# kicker_controller.net
KiCad netlist of a schematic drawn in EAGLE
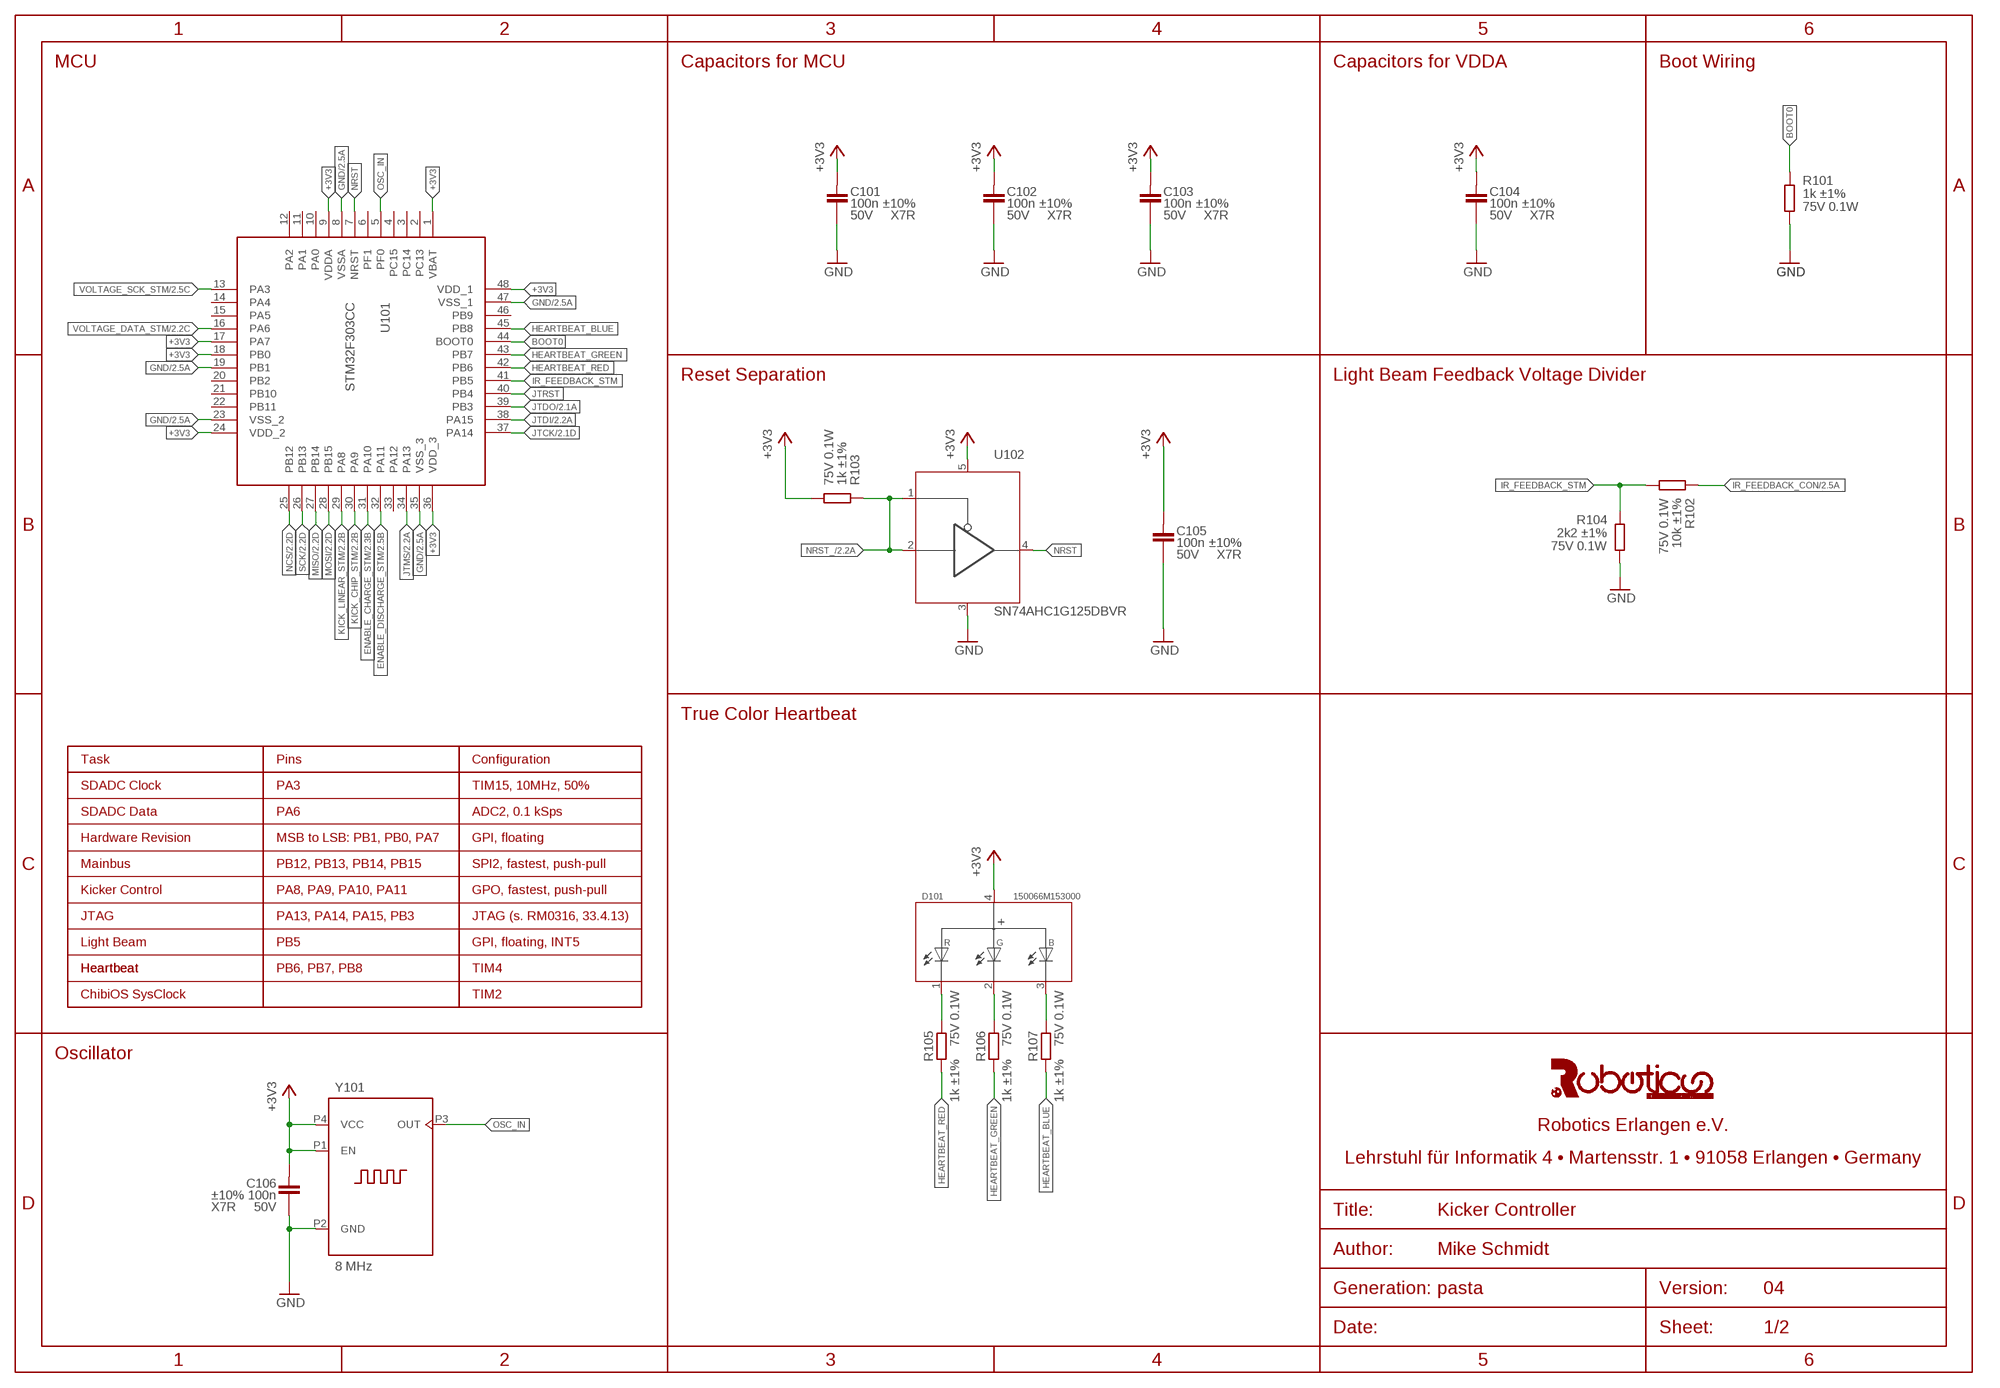
[diagram p0: schematic, sheet 1]
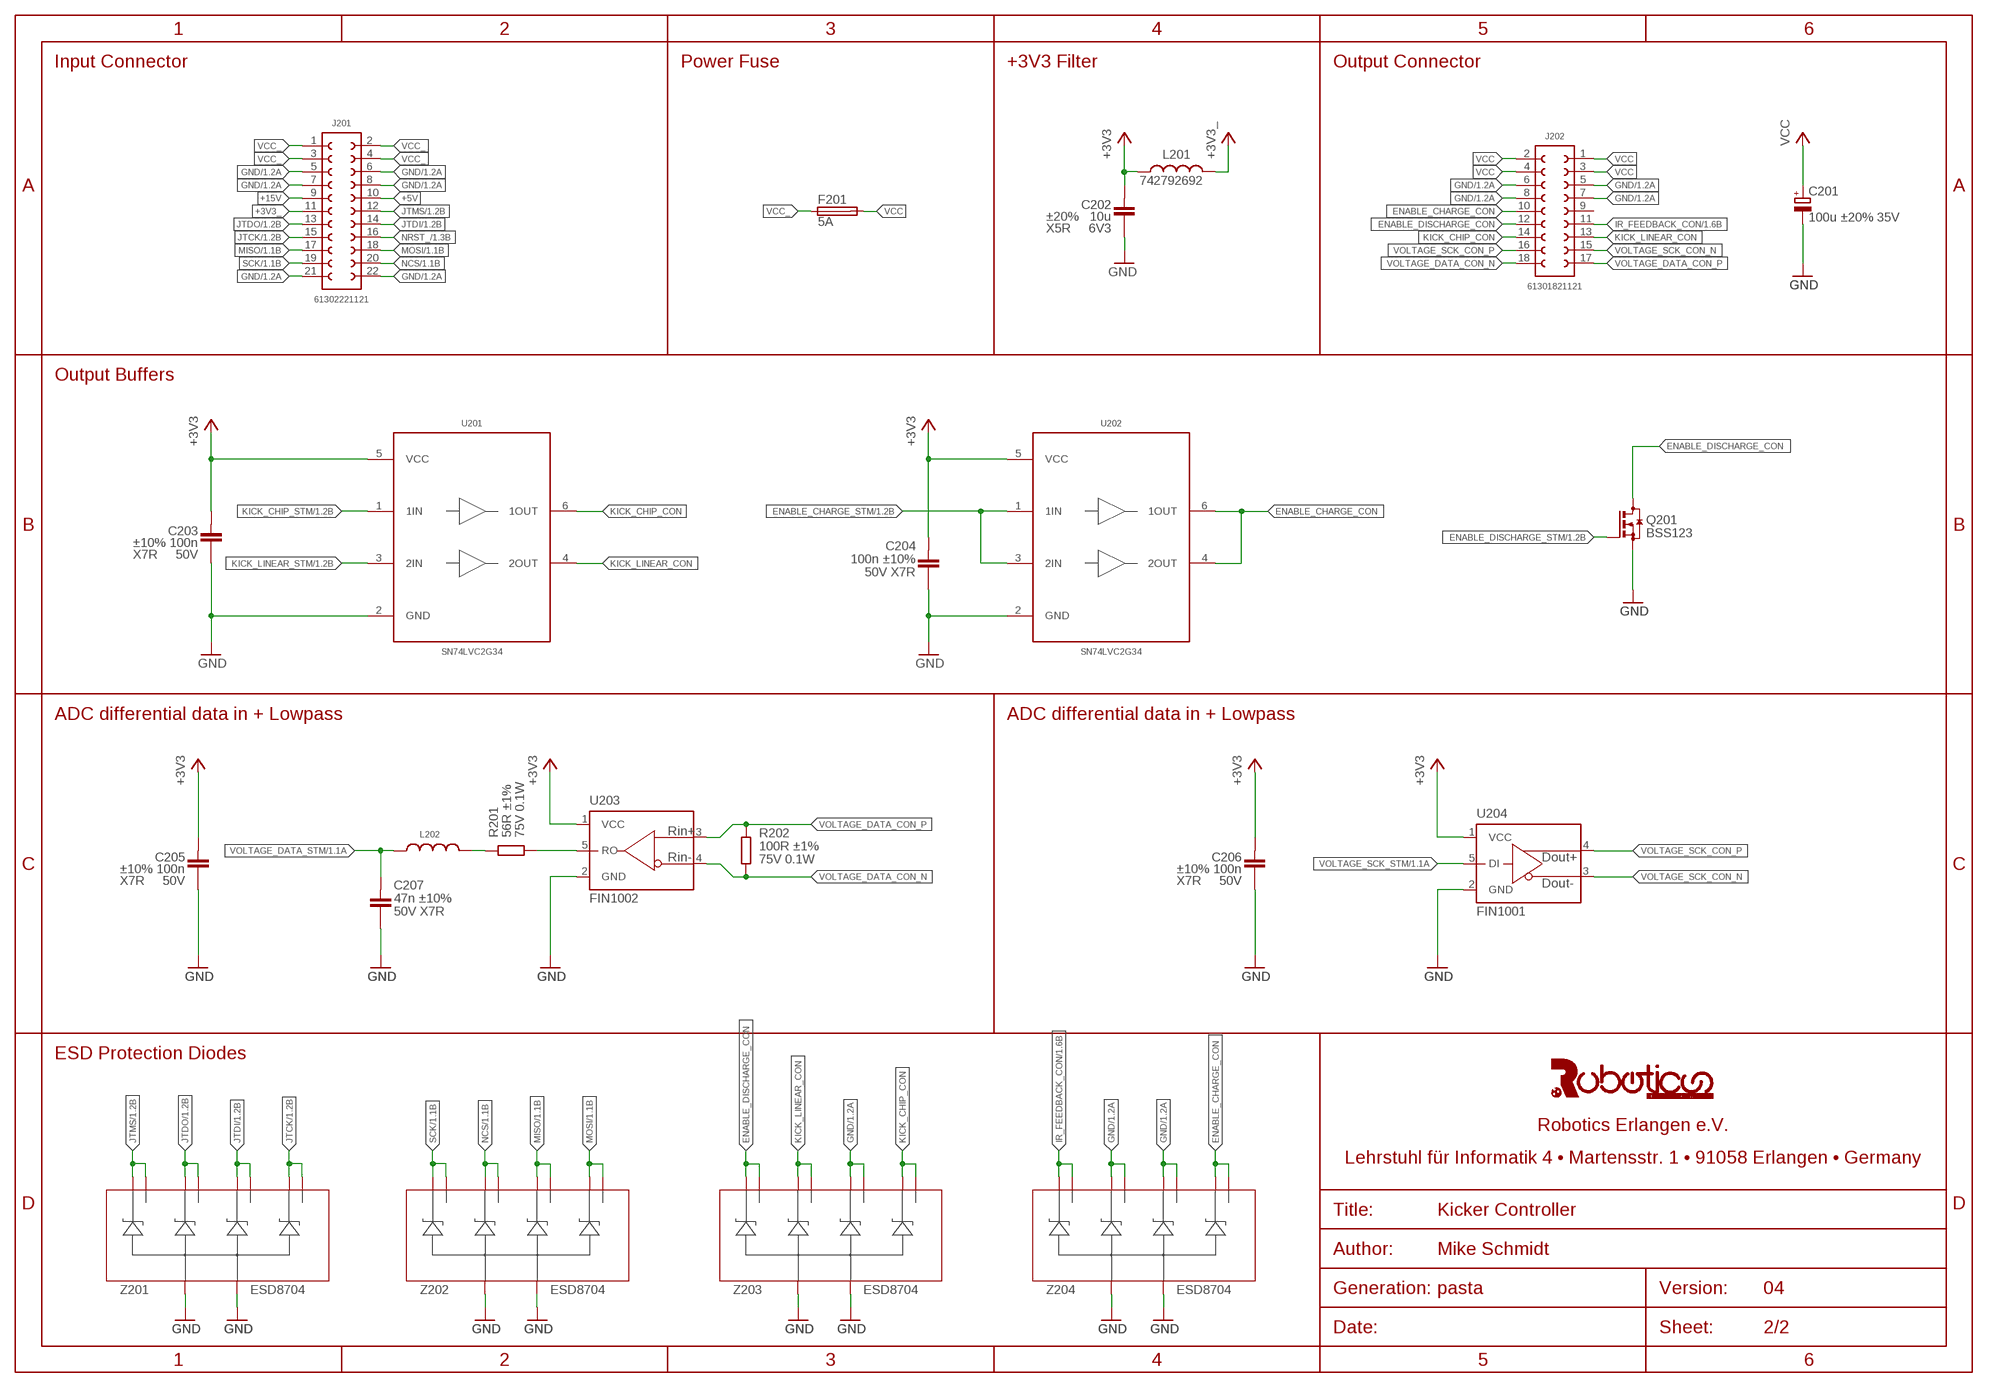
[diagram p1: schematic, sheet 2]

(export (version "E")
  (design (tool "Eeschema 10.0.6"))
  (components
    (comp (ref "C201")
      (value "100u ±20% 35V")
      (footprint "eagle-import:865080545012")
      (fields (field (name "MF") "Würth Elektronik") (field (name "MPN") "865080545012"))
      (libsource (lib "eagle-import") (part "865080545012"))
    )
    (comp (ref "C202")
      (value "10u ±20% 6V3 X5R")
      (footprint "eagle-import:C0603")
      (fields
        (field (name "CAPACITANCE") "10u")
        (field (name "DIELECTRIC") "X5R")
        (field (name "MF") "Würth Elektronik")
        (field (name "MPN") "885012106006")
        (field (name "TOLERANCE") "±20%")
        (field (name "VOLTAGE") "6V3")
      )
      (libsource (lib "eagle-import") (part "C(?)060310UF,6.3V,"))
    )
    (comp (ref "C203")
      (value "100n ±10% 50V X7R")
      (footprint "eagle-import:C0603")
      (fields
        (field (name "CAPACITANCE") "100n")
        (field (name "DIELECTRIC") "X7R")
        (field (name "MF") "Würth Elektronik")
        (field (name "MPN") "885012206095")
        (field (name "TOLERANCE") "±10%")
        (field (name "VOLTAGE") "50V")
      )
      (libsource (lib "eagle-import") (part "C(?)0603100NF,50V,"))
    )
    (comp (ref "C204")
      (value "100n ±10% 50V X7R")
      (footprint "eagle-import:C0603")
      (fields
        (field (name "LINE1") "100n ±10%")
        (field (name "LINE2") "50V X7R")
        (field (name "MF") "Würth Elektronik")
        (field (name "MPN") "885012206095")
        (field (name "TOLERANCE") "±10%")
      )
      (libsource (lib "eagle-import") (part "C(?)0603100NF,50V,"))
    )
    (comp (ref "C205")
      (value "100n ±10% 50V X7R")
      (footprint "eagle-import:C0603")
      (fields
        (field (name "CAPACITANCE") "100n")
        (field (name "DIELECTRIC") "X7R")
        (field (name "MF") "Würth Elektronik")
        (field (name "MPN") "885012206095")
        (field (name "TOLERANCE") "±10%")
        (field (name "VOLTAGE") "50V")
      )
      (libsource (lib "eagle-import") (part "C(?)0603100NF,50V,"))
    )
    (comp (ref "C206")
      (value "100n ±10% 50V X7R")
      (footprint "eagle-import:C0603")
      (fields
        (field (name "CAPACITANCE") "100n")
        (field (name "DIELECTRIC") "X7R")
        (field (name "MF") "Würth Elektronik")
        (field (name "MPN") "885012206095")
        (field (name "TOLERANCE") "±10%")
        (field (name "VOLTAGE") "50V")
      )
      (libsource (lib "eagle-import") (part "C(?)0603100NF,50V,"))
    )
    (comp (ref "C207")
      (value "47n ±10% 50V X7R")
      (footprint "eagle-import:C0603")
      (fields
        (field (name "LINE1") "47n ±10%")
        (field (name "LINE2") "50V X7R")
        (field (name "MF") "Würth Elektronik")
        (field (name "MPN") "885012206093")
        (field (name "TOLERANCE") "±10%")
      )
      (libsource (lib "eagle-import") (part "C(?)060347NF,50V,"))
    )
    (comp (ref "F201")
      (value "5A")
      (footprint "eagle-import:157T")
      (fields (field (name "MF") "Littelfuse") (field (name "MPN") "0157005.DRT"))
      (libsource (lib "eagle-import") (part "0157DRT005."))
    )
    (comp (ref "J201")
      (value "61302221121")
      (footprint "eagle-import:61302221121")
      (fields (field (name "MF") "Würth Elektronik"))
      (libsource (lib "eagle-import") (part "61302221121"))
    )
    (comp (ref "J202")
      (value "61301821121")
      (footprint "eagle-import:61301821121")
      (fields (field (name "MF") "Würth Elektronik"))
      (libsource (lib "eagle-import") (part "61301821121"))
    )
    (comp (ref "L201")
      (value "742792692")
      (footprint "eagle-import:WE-CBF_0603(W=2.6)")
      (fields (field (name "MF") "Würth Elektronik"))
      (libsource (lib "eagle-import") (part "742792692"))
    )
    (comp (ref "L202")
      (value "WE-GFH_4532_7447669212")
      (footprint "eagle-import:WE-GFH_4532")
      (libsource (lib "eagle-import") (part "WE-GFH_4532_7447669212"))
    )
    (comp (ref "Q201")
      (value "BSS123")
      (footprint "eagle-import:SOT23")
      (libsource (lib "eagle-import") (part "BSS123"))
    )
    (comp (ref "R201")
      (value "56R ±1% 75V 0.1W")
      (footprint "eagle-import:R0603")
      (fields
        (field (name "LINE1") "56R ±1%")
        (field (name "LINE2") "75V 0.1W")
        (field (name "MF") "YAGEO")
        (field (name "MPN") "RC0603FR-0756RL")
        (field (name "POWER") "0.1W")
      )
      (libsource (lib "eagle-import") (part "R(?)060356R,75V,0.1W,"))
    )
    (comp (ref "R202")
      (value "100R ±1% 75V 0.1W")
      (footprint "eagle-import:R0603")
      (fields
        (field (name "LINE1") "100R ±1%")
        (field (name "LINE2") "75V 0.1W")
        (field (name "MF") "YAGEO")
        (field (name "MPN") "RC0603FR-07100RL")
        (field (name "POWER") "0.1W")
      )
      (libsource (lib "eagle-import") (part "R(?)0603100R,75V,0.1W,"))
    )
    (comp (ref "U201")
      (value "SN74LVC2G34")
      (footprint "eagle-import:SOT")
      (fields (field (name "MF") "Texas Instruments"))
      (libsource (lib "eagle-import") (part "SN74LVC2G34"))
    )
    (comp (ref "U202")
      (value "SN74LVC2G34")
      (footprint "eagle-import:SOT")
      (fields (field (name "MF") "Texas Instruments"))
      (libsource (lib "eagle-import") (part "SN74LVC2G34"))
    )
    (comp (ref "U203")
      (value "FIN1002")
      (footprint "eagle-import:SOT23-5")
      (libsource (lib "eagle-import") (part "FIN1002"))
    )
    (comp (ref "U204")
      (value "FIN1001")
      (footprint "eagle-import:SOT23-5")
      (libsource (lib "eagle-import") (part "FIN1001"))
    )
    (comp (ref "Z201")
      (value "ESD8704")
      (footprint "eagle-import:UDFN10")
      (fields (field (name "MF") "ON Semiconductor") (field (name "MPN") "ESD8704MUTAG"))
      (libsource (lib "eagle-import") (part "ESD8704"))
    )
    (comp (ref "Z202")
      (value "ESD8704")
      (footprint "eagle-import:UDFN10")
      (fields (field (name "MF") "ON Semiconductor") (field (name "MPN") "ESD8704MUTAG"))
      (libsource (lib "eagle-import") (part "ESD8704"))
    )
    (comp (ref "Z203")
      (value "ESD8704")
      (footprint "eagle-import:UDFN10")
      (fields (field (name "MF") "ON Semiconductor") (field (name "MPN") "ESD8704MUTAG"))
      (libsource (lib "eagle-import") (part "ESD8704"))
    )
    (comp (ref "Z204")
      (value "ESD8704")
      (footprint "eagle-import:UDFN10")
      (fields (field (name "MF") "ON Semiconductor") (field (name "MPN") "ESD8704MUTAG"))
      (libsource (lib "eagle-import") (part "ESD8704"))
    )
    (comp (ref "C101")
      (value "100n ±10% 50V X7R")
      (footprint "eagle-import:C0603")
      (fields
        (field (name "CAPACITANCE") "100n")
        (field (name "DIELECTRIC") "X7R")
        (field (name "MF") "Würth Elektronik")
        (field (name "MPN") "885012206095")
        (field (name "TOLERANCE") "±10%")
        (field (name "VOLTAGE") "50V")
      )
      (libsource (lib "eagle-import") (part "C(?)0603100NF,50V,"))
    )
    (comp (ref "C102")
      (value "100n ±10% 50V X7R")
      (footprint "eagle-import:C0603")
      (fields
        (field (name "CAPACITANCE") "100n")
        (field (name "DIELECTRIC") "X7R")
        (field (name "MF") "Würth Elektronik")
        (field (name "MPN") "885012206095")
        (field (name "TOLERANCE") "±10%")
        (field (name "VOLTAGE") "50V")
      )
      (libsource (lib "eagle-import") (part "C(?)0603100NF,50V,"))
    )
    (comp (ref "C103")
      (value "100n ±10% 50V X7R")
      (footprint "eagle-import:C0603")
      (fields
        (field (name "CAPACITANCE") "100n")
        (field (name "DIELECTRIC") "X7R")
        (field (name "MF") "Würth Elektronik")
        (field (name "MPN") "885012206095")
        (field (name "TOLERANCE") "±10%")
        (field (name "VOLTAGE") "50V")
      )
      (libsource (lib "eagle-import") (part "C(?)0603100NF,50V,"))
    )
    (comp (ref "C104")
      (value "100n ±10% 50V X7R")
      (footprint "eagle-import:C0603")
      (fields
        (field (name "CAPACITANCE") "100n")
        (field (name "DIELECTRIC") "X7R")
        (field (name "MF") "Würth Elektronik")
        (field (name "MPN") "885012206095")
        (field (name "TOLERANCE") "±10%")
        (field (name "VOLTAGE") "50V")
      )
      (libsource (lib "eagle-import") (part "C(?)0603100NF,50V,"))
    )
    (comp (ref "C105")
      (value "100n ±10% 50V X7R")
      (footprint "eagle-import:C0603")
      (fields
        (field (name "CAPACITANCE") "100n")
        (field (name "DIELECTRIC") "X7R")
        (field (name "MF") "Würth Elektronik")
        (field (name "MPN") "885012206095")
        (field (name "TOLERANCE") "±10%")
        (field (name "VOLTAGE") "50V")
      )
      (libsource (lib "eagle-import") (part "C(?)0603100NF,50V,"))
    )
    (comp (ref "C106")
      (value "100n ±10% 50V X7R")
      (footprint "eagle-import:C0603")
      (fields
        (field (name "CAPACITANCE") "100n")
        (field (name "DIELECTRIC") "X7R")
        (field (name "MF") "Würth Elektronik")
        (field (name "MPN") "885012206095")
        (field (name "TOLERANCE") "±10%")
        (field (name "VOLTAGE") "50V")
      )
      (libsource (lib "eagle-import") (part "C(?)0603100NF,50V,"))
    )
    (comp (ref "D101")
      (value "150066M153000")
      (footprint "eagle-import:WL-SFCX_0606")
      (fields (field (name "MF") "Würth Elektronik"))
      (libsource (lib "eagle-import") (part "150066M153000"))
    )
    (comp (ref "R101")
      (value "1k ±1% 75V 0.1W")
      (footprint "eagle-import:R0603")
      (fields
        (field (name "LINE1") "1k ±1%")
        (field (name "LINE2") "75V 0.1W")
        (field (name "MF") "YAGEO")
        (field (name "MPN") "RC0603FR-071KL")
        (field (name "POWER") "0.1W")
      )
      (libsource (lib "eagle-import") (part "R(?)06031.0K,75V,0.1W,"))
    )
    (comp (ref "R102")
      (value "10k ±1% 75V 0.1W")
      (footprint "eagle-import:R0603")
      (fields
        (field (name "LINE1") "10k ±1%")
        (field (name "LINE2") "75V 0.1W")
        (field (name "MF") "YAGEO")
        (field (name "MPN") "RC0603FR-0710KL")
        (field (name "POWER") "0.1W")
      )
      (libsource (lib "eagle-import") (part "R(?)060310K,75V,0.1W,"))
    )
    (comp (ref "R103")
      (value "1k ±1% 75V 0.1W")
      (footprint "eagle-import:R0603")
      (fields
        (field (name "LINE1") "1k ±1%")
        (field (name "LINE2") "75V 0.1W")
        (field (name "MF") "YAGEO")
        (field (name "MPN") "RC0603FR-071KL")
        (field (name "POWER") "0.1W")
      )
      (libsource (lib "eagle-import") (part "R(?)06031.0K,75V,0.1W,"))
    )
    (comp (ref "R104")
      (value "2k2 ±1% 75V 0.1W")
      (footprint "eagle-import:R0603")
      (fields
        (field (name "LINE1") "2k2 ±1%")
        (field (name "LINE2") "75V 0.1W")
        (field (name "MF") "YAGEO")
        (field (name "MPN") "RC0603FR-072K2L")
        (field (name "POWER") "0.1W")
      )
      (libsource (lib "eagle-import") (part "R(?)06032.2K,75V,0.1W,"))
    )
    (comp (ref "R105")
      (value "1k ±1% 75V 0.1W")
      (footprint "eagle-import:R0603")
      (fields
        (field (name "LINE1") "1k ±1%")
        (field (name "LINE2") "75V 0.1W")
        (field (name "MF") "YAGEO")
        (field (name "MPN") "RC0603FR-071KL")
        (field (name "POWER") "0.1W")
      )
      (libsource (lib "eagle-import") (part "R(?)06031.0K,75V,0.1W,"))
    )
    (comp (ref "R106")
      (value "1k ±1% 75V 0.1W")
      (footprint "eagle-import:R0603")
      (fields
        (field (name "LINE1") "1k ±1%")
        (field (name "LINE2") "75V 0.1W")
        (field (name "MF") "YAGEO")
        (field (name "MPN") "RC0603FR-071KL")
        (field (name "POWER") "0.1W")
      )
      (libsource (lib "eagle-import") (part "R(?)06031.0K,75V,0.1W,"))
    )
    (comp (ref "R107")
      (value "1k ±1% 75V 0.1W")
      (footprint "eagle-import:R0603")
      (fields
        (field (name "LINE1") "1k ±1%")
        (field (name "LINE2") "75V 0.1W")
        (field (name "MF") "YAGEO")
        (field (name "MPN") "RC0603FR-071KL")
        (field (name "POWER") "0.1W")
      )
      (libsource (lib "eagle-import") (part "R(?)06031.0K,75V,0.1W,"))
    )
    (comp (ref "U101")
      (value "STM32F303CC")
      (footprint "eagle-import:LQFP48")
      (fields (field (name "MF") "STMicroelectronics") (field (name "MPN") "STM32F303CCT6"))
      (libsource (lib "eagle-import") (part "STM32F303CC"))
    )
    (comp (ref "U102")
      (value "SN74AHC1G125DBVR")
      (footprint "eagle-import:SOT23-5")
      (fields (field (name "MF") "Texas Instruments"))
      (libsource (lib "eagle-import") (part "SN74AHC1G125DBVR"))
    )
    (comp (ref "Y101")
      (value "8 MHz")
      (footprint "eagle-import:830207192009")
      (fields (field (name "MF") "Würth Elektronik") (field (name "MPN") "830207192009"))
      (libsource (lib "eagle-import") (part "830200971920"))
    )
  )
  (nets
    (net (code "1") (name "+3V3") (class "Default")
      (node (ref "C101") (pin "1") (pinfunction "1_1") (pintype "passive"))
      (node (ref "C102") (pin "1") (pinfunction "1_1") (pintype "passive"))
      (node (ref "C103") (pin "1") (pinfunction "1_1") (pintype "passive"))
      (node (ref "C104") (pin "1") (pinfunction "1_1") (pintype "passive"))
      (node (ref "C105") (pin "1") (pinfunction "1_1") (pintype "passive"))
      (node (ref "C106") (pin "1") (pinfunction "1_1") (pintype "passive"))
      (node (ref "C202") (pin "1") (pinfunction "1_1") (pintype "passive"))
      (node (ref "C203") (pin "1") (pinfunction "1_1") (pintype "passive"))
      (node (ref "C204") (pin "1") (pinfunction "1_1") (pintype "passive"))
      (node (ref "C205") (pin "1") (pinfunction "1_1") (pintype "passive"))
      (node (ref "C206") (pin "1") (pinfunction "1_1") (pintype "passive"))
      (node (ref "D101") (pin "4") (pinfunction "4_4") (pintype "passive"))
      (node (ref "L201") (pin "2") (pinfunction "2_2") (pintype "passive"))
      (node (ref "R103") (pin "1") (pinfunction "1_1") (pintype "passive"))
      (node (ref "U101") (pin "1") (pinfunction "VBAT_1") (pintype "power_in"))
      (node (ref "U101") (pin "17") (pinfunction "PA7_17") (pintype "bidirectional"))
      (node (ref "U101") (pin "18") (pinfunction "PB0_18") (pintype "bidirectional"))
      (node (ref "U101") (pin "24") (pinfunction "VDD_2_24") (pintype "power_in"))
      (node (ref "U101") (pin "36") (pinfunction "VDD_3_36") (pintype "power_in"))
      (node (ref "U101") (pin "48") (pinfunction "VDD_1_48") (pintype "power_in"))
      (node (ref "U101") (pin "9") (pinfunction "VDDA_9") (pintype "power_in"))
      (node (ref "U102") (pin "5") (pinfunction "VCC_5") (pintype "power_in"))
      (node (ref "U201") (pin "5") (pinfunction "VCC_5") (pintype "power_in"))
      (node (ref "U202") (pin "5") (pinfunction "VCC_5") (pintype "power_in"))
      (node (ref "U203") (pin "1") (pinfunction "VCC_1") (pintype "bidirectional"))
      (node (ref "U204") (pin "1") (pinfunction "VCC_1") (pintype "bidirectional"))
      (node (ref "Y101") (pin "P1") (pinfunction "EN_P1") (pintype "input"))
      (node (ref "Y101") (pin "P4") (pinfunction "VCC_P4") (pintype "power_in"))
    )
    (net (code "2") (name "+3V3_") (class "Default")
      (node (ref "J201") (pin "11") (pinfunction "11_11") (pintype "passive"))
      (node (ref "L201") (pin "1") (pinfunction "1_1") (pintype "passive"))
    )
    (net (code "3") (name "+5V") (class "Default")
      (node (ref "J201") (pin "10") (pinfunction "10_10") (pintype "passive"))
    )
    (net (code "4") (name "+15V") (class "Default")
      (node (ref "J201") (pin "9") (pinfunction "9_9") (pintype "passive"))
    )
    (net (code "5") (name "BOOT0") (class "Default")
      (node (ref "R101") (pin "2") (pinfunction "2_2") (pintype "passive"))
      (node (ref "U101") (pin "44") (pinfunction "BOOT0_44") (pintype "bidirectional"))
    )
    (net (code "6") (name "ENABLE_CHARGE_CON") (class "Default")
      (node (ref "J202") (pin "10") (pinfunction "10_10") (pintype "passive"))
      (node (ref "U202") (pin "4") (pinfunction "2OUT_4") (pintype "output"))
      (node (ref "U202") (pin "6") (pinfunction "1OUT_6") (pintype "output"))
      (node (ref "Z204") (pin "5") (pinfunction "C4_5") (pintype "passive"))
      (node (ref "Z204") (pin "6") (pinfunction "D4_6") (pintype "passive"))
    )
    (net (code "7") (name "ENABLE_CHARGE_STM") (class "Default")
      (node (ref "U101") (pin "31") (pinfunction "PA10_31") (pintype "bidirectional"))
      (node (ref "U202") (pin "1") (pinfunction "1IN_1") (pintype "input"))
      (node (ref "U202") (pin "3") (pinfunction "2IN_3") (pintype "input"))
    )
    (net (code "8") (name "ENABLE_DISCHARGE_CON") (class "Default")
      (node (ref "J202") (pin "12") (pinfunction "12_12") (pintype "passive"))
      (node (ref "Q201") (pin "3") (pinfunction "D_3") (pintype "passive"))
      (node (ref "Z203") (pin "1") (pinfunction "C1_1") (pintype "passive"))
      (node (ref "Z203") (pin "10") (pinfunction "D1_10") (pintype "passive"))
    )
    (net (code "9") (name "ENABLE_DISCHARGE_STM") (class "Default")
      (node (ref "Q201") (pin "1") (pinfunction "G_1") (pintype "passive"))
      (node (ref "U101") (pin "32") (pinfunction "PA11_32") (pintype "bidirectional"))
    )
    (net (code "10") (name "GND") (class "Default")
      (node (ref "C101") (pin "2") (pinfunction "2_2") (pintype "passive"))
      (node (ref "C102") (pin "2") (pinfunction "2_2") (pintype "passive"))
      (node (ref "C103") (pin "2") (pinfunction "2_2") (pintype "passive"))
      (node (ref "C104") (pin "2") (pinfunction "2_2") (pintype "passive"))
      (node (ref "C105") (pin "2") (pinfunction "2_2") (pintype "passive"))
      (node (ref "C106") (pin "2") (pinfunction "2_2") (pintype "passive"))
      (node (ref "C201") (pin "N") (pinfunction "-_N") (pintype "passive"))
      (node (ref "C202") (pin "2") (pinfunction "2_2") (pintype "passive"))
      (node (ref "C203") (pin "2") (pinfunction "2_2") (pintype "passive"))
      (node (ref "C204") (pin "2") (pinfunction "2_2") (pintype "passive"))
      (node (ref "C205") (pin "2") (pinfunction "2_2") (pintype "passive"))
      (node (ref "C206") (pin "2") (pinfunction "2_2") (pintype "passive"))
      (node (ref "C207") (pin "2") (pinfunction "2_2") (pintype "passive"))
      (node (ref "J201") (pin "21") (pinfunction "21_21") (pintype "passive"))
      (node (ref "J201") (pin "22") (pinfunction "22_22") (pintype "passive"))
      (node (ref "J201") (pin "5") (pinfunction "5_5") (pintype "passive"))
      (node (ref "J201") (pin "6") (pinfunction "6_6") (pintype "passive"))
      (node (ref "J201") (pin "7") (pinfunction "7_7") (pintype "passive"))
      (node (ref "J201") (pin "8") (pinfunction "8_8") (pintype "passive"))
      (node (ref "J202") (pin "5") (pinfunction "5_5") (pintype "passive"))
      (node (ref "J202") (pin "6") (pinfunction "6_6") (pintype "passive"))
      (node (ref "J202") (pin "7") (pinfunction "7_7") (pintype "passive"))
      (node (ref "J202") (pin "8") (pinfunction "8_8") (pintype "passive"))
      (node (ref "Q201") (pin "2") (pinfunction "S_2") (pintype "passive"))
      (node (ref "R101") (pin "1") (pinfunction "1_1") (pintype "passive"))
      (node (ref "R104") (pin "1") (pinfunction "1_1") (pintype "passive"))
      (node (ref "U101") (pin "19") (pinfunction "PB1_19") (pintype "bidirectional"))
      (node (ref "U101") (pin "23") (pinfunction "VSS_2_23") (pintype "power_in"))
      (node (ref "U101") (pin "35") (pinfunction "VSS_3_35") (pintype "power_in"))
      (node (ref "U101") (pin "47") (pinfunction "VSS_1_47") (pintype "power_in"))
      (node (ref "U101") (pin "8") (pinfunction "VSSA_8") (pintype "power_in"))
      (node (ref "U102") (pin "3") (pinfunction "GND_3") (pintype "power_in"))
      (node (ref "U201") (pin "2") (pinfunction "GND_2") (pintype "power_in"))
      (node (ref "U202") (pin "2") (pinfunction "GND_2") (pintype "power_in"))
      (node (ref "U203") (pin "2") (pinfunction "GND_2") (pintype "bidirectional"))
      (node (ref "U204") (pin "2") (pinfunction "GND_2") (pintype "bidirectional"))
      (node (ref "Y101") (pin "P2") (pinfunction "GND_P2") (pintype "power_in"))
      (node (ref "Z201") (pin "3") (pinfunction "A_3") (pintype "passive"))
      (node (ref "Z201") (pin "8") (pinfunction "A_8") (pintype "passive"))
      (node (ref "Z202") (pin "3") (pinfunction "A_3") (pintype "passive"))
      (node (ref "Z202") (pin "8") (pinfunction "A_8") (pintype "passive"))
      (node (ref "Z203") (pin "3") (pinfunction "A_3") (pintype "passive"))
      (node (ref "Z203") (pin "4") (pinfunction "C3_4") (pintype "passive"))
      (node (ref "Z203") (pin "7") (pinfunction "D3_7") (pintype "passive"))
      (node (ref "Z203") (pin "8") (pinfunction "A_8") (pintype "passive"))
      (node (ref "Z204") (pin "2") (pinfunction "C2_2") (pintype "passive"))
      (node (ref "Z204") (pin "3") (pinfunction "A_3") (pintype "passive"))
      (node (ref "Z204") (pin "4") (pinfunction "C3_4") (pintype "passive"))
      (node (ref "Z204") (pin "7") (pinfunction "D3_7") (pintype "passive"))
      (node (ref "Z204") (pin "8") (pinfunction "A_8") (pintype "passive"))
      (node (ref "Z204") (pin "9") (pinfunction "D2_9") (pintype "passive"))
    )
    (net (code "11") (name "HEARTBEAT_BLUE") (class "Default")
      (node (ref "R107") (pin "2") (pinfunction "2_2") (pintype "passive"))
      (node (ref "U101") (pin "45") (pinfunction "PB8_45") (pintype "bidirectional"))
    )
    (net (code "12") (name "HEARTBEAT_GREEN") (class "Default")
      (node (ref "R106") (pin "2") (pinfunction "2_2") (pintype "passive"))
      (node (ref "U101") (pin "43") (pinfunction "PB7_43") (pintype "bidirectional"))
    )
    (net (code "13") (name "HEARTBEAT_RED") (class "Default")
      (node (ref "R105") (pin "2") (pinfunction "2_2") (pintype "passive"))
      (node (ref "U101") (pin "42") (pinfunction "PB6_42") (pintype "bidirectional"))
    )
    (net (code "14") (name "IR_FEEDBACK_CON") (class "Default")
      (node (ref "J202") (pin "11") (pinfunction "11_11") (pintype "passive"))
      (node (ref "R102") (pin "2") (pinfunction "2_2") (pintype "passive"))
      (node (ref "Z204") (pin "1") (pinfunction "C1_1") (pintype "passive"))
      (node (ref "Z204") (pin "10") (pinfunction "D1_10") (pintype "passive"))
    )
    (net (code "15") (name "IR_FEEDBACK_STM") (class "Default")
      (node (ref "R102") (pin "1") (pinfunction "1_1") (pintype "passive"))
      (node (ref "R104") (pin "2") (pinfunction "2_2") (pintype "passive"))
      (node (ref "U101") (pin "41") (pinfunction "PB5_41") (pintype "bidirectional"))
    )
    (net (code "16") (name "JTCK") (class "Default")
      (node (ref "J201") (pin "15") (pinfunction "15_15") (pintype "passive"))
      (node (ref "U101") (pin "37") (pinfunction "PA14_37") (pintype "bidirectional"))
      (node (ref "Z201") (pin "5") (pinfunction "C4_5") (pintype "passive"))
      (node (ref "Z201") (pin "6") (pinfunction "D4_6") (pintype "passive"))
    )
    (net (code "17") (name "JTDI") (class "Default")
      (node (ref "J201") (pin "14") (pinfunction "14_14") (pintype "passive"))
      (node (ref "U101") (pin "38") (pinfunction "PA15_38") (pintype "bidirectional"))
      (node (ref "Z201") (pin "4") (pinfunction "C3_4") (pintype "passive"))
      (node (ref "Z201") (pin "7") (pinfunction "D3_7") (pintype "passive"))
    )
    (net (code "18") (name "JTDO") (class "Default")
      (node (ref "J201") (pin "13") (pinfunction "13_13") (pintype "passive"))
      (node (ref "U101") (pin "39") (pinfunction "PB3_39") (pintype "bidirectional"))
      (node (ref "Z201") (pin "2") (pinfunction "C2_2") (pintype "passive"))
      (node (ref "Z201") (pin "9") (pinfunction "D2_9") (pintype "passive"))
    )
    (net (code "19") (name "JTMS") (class "Default")
      (node (ref "J201") (pin "12") (pinfunction "12_12") (pintype "passive"))
      (node (ref "U101") (pin "34") (pinfunction "PA13_34") (pintype "bidirectional"))
      (node (ref "Z201") (pin "1") (pinfunction "C1_1") (pintype "passive"))
      (node (ref "Z201") (pin "10") (pinfunction "D1_10") (pintype "passive"))
    )
    (net (code "20") (name "JTRST") (class "Default")
      (node (ref "U101") (pin "40") (pinfunction "PB4_40") (pintype "bidirectional"))
    )
    (net (code "21") (name "KICK_CHIP_CON") (class "Default")
      (node (ref "J202") (pin "14") (pinfunction "14_14") (pintype "passive"))
      (node (ref "U201") (pin "6") (pinfunction "1OUT_6") (pintype "output"))
      (node (ref "Z203") (pin "5") (pinfunction "C4_5") (pintype "passive"))
      (node (ref "Z203") (pin "6") (pinfunction "D4_6") (pintype "passive"))
    )
    (net (code "22") (name "KICK_CHIP_STM") (class "Default")
      (node (ref "U101") (pin "30") (pinfunction "PA9_30") (pintype "bidirectional"))
      (node (ref "U201") (pin "1") (pinfunction "1IN_1") (pintype "input"))
    )
    (net (code "23") (name "KICK_LINEAR_CON") (class "Default")
      (node (ref "J202") (pin "13") (pinfunction "13_13") (pintype "passive"))
      (node (ref "U201") (pin "4") (pinfunction "2OUT_4") (pintype "output"))
      (node (ref "Z203") (pin "2") (pinfunction "C2_2") (pintype "passive"))
      (node (ref "Z203") (pin "9") (pinfunction "D2_9") (pintype "passive"))
    )
    (net (code "24") (name "KICK_LINEAR_STM") (class "Default")
      (node (ref "U101") (pin "29") (pinfunction "PA8_29") (pintype "bidirectional"))
      (node (ref "U201") (pin "3") (pinfunction "2IN_3") (pintype "input"))
    )
    (net (code "25") (name "MISO") (class "Default")
      (node (ref "J201") (pin "17") (pinfunction "17_17") (pintype "passive"))
      (node (ref "U101") (pin "27") (pinfunction "PB14_27") (pintype "bidirectional"))
      (node (ref "Z202") (pin "4") (pinfunction "C3_4") (pintype "passive"))
      (node (ref "Z202") (pin "7") (pinfunction "D3_7") (pintype "passive"))
    )
    (net (code "26") (name "MOSI") (class "Default")
      (node (ref "J201") (pin "18") (pinfunction "18_18") (pintype "passive"))
      (node (ref "U101") (pin "28") (pinfunction "PB15_28") (pintype "bidirectional"))
      (node (ref "Z202") (pin "5") (pinfunction "C4_5") (pintype "passive"))
      (node (ref "Z202") (pin "6") (pinfunction "D4_6") (pintype "passive"))
    )
    (net (code "27") (name "NCS") (class "Default")
      (node (ref "J201") (pin "20") (pinfunction "20_20") (pintype "passive"))
      (node (ref "U101") (pin "25") (pinfunction "PB12_25") (pintype "bidirectional"))
      (node (ref "Z202") (pin "2") (pinfunction "C2_2") (pintype "passive"))
      (node (ref "Z202") (pin "9") (pinfunction "D2_9") (pintype "passive"))
    )
    (net (code "28") (name "NRST") (class "Default")
      (node (ref "U101") (pin "7") (pinfunction "NRST_7") (pintype "bidirectional"))
      (node (ref "U102") (pin "4") (pinfunction "O_4") (pintype "tri_state"))
    )
    (net (code "29") (name "NRST_") (class "Default")
      (node (ref "J201") (pin "16") (pinfunction "16_16") (pintype "passive"))
      (node (ref "R103") (pin "2") (pinfunction "2_2") (pintype "passive"))
      (node (ref "U102") (pin "1") (pinfunction "OE_1") (pintype "input"))
      (node (ref "U102") (pin "2") (pinfunction "I_2") (pintype "input"))
    )
    (net (code "30") (name "Net-(D101-B)") (class "Default")
      (node (ref "D101") (pin "3") (pinfunction "B_3") (pintype "passive"))
      (node (ref "R107") (pin "1") (pinfunction "1_1") (pintype "passive"))
    )
    (net (code "31") (name "Net-(D101-G)") (class "Default")
      (node (ref "D101") (pin "2") (pinfunction "G_2") (pintype "passive"))
      (node (ref "R106") (pin "1") (pinfunction "1_1") (pintype "passive"))
    )
    (net (code "32") (name "Net-(D101-R)") (class "Default")
      (node (ref "D101") (pin "1") (pinfunction "R_1") (pintype "passive"))
      (node (ref "R105") (pin "1") (pinfunction "1_1") (pintype "passive"))
    )
    (net (code "33") (name "Net-(L202-Pad2)") (class "Default")
      (node (ref "L202") (pin "2") (pinfunction "2_2") (pintype "passive"))
      (node (ref "R201") (pin "2") (pinfunction "2_2") (pintype "passive"))
    )
    (net (code "34") (name "Net-(U203-RO)") (class "Default")
      (node (ref "R201") (pin "1") (pinfunction "1_1") (pintype "passive"))
      (node (ref "U203") (pin "5") (pinfunction "RO_5") (pintype "output"))
    )
    (net (code "35") (name "OSC_IN") (class "Default")
      (node (ref "U101") (pin "5") (pinfunction "PF0_5") (pintype "bidirectional"))
      (node (ref "Y101") (pin "P3") (pinfunction "OUT_P3") (pintype "output"))
    )
    (net (code "36") (name "SCK") (class "Default")
      (node (ref "J201") (pin "19") (pinfunction "19_19") (pintype "passive"))
      (node (ref "U101") (pin "26") (pinfunction "PB13_26") (pintype "bidirectional"))
      (node (ref "Z202") (pin "1") (pinfunction "C1_1") (pintype "passive"))
      (node (ref "Z202") (pin "10") (pinfunction "D1_10") (pintype "passive"))
    )
    (net (code "37") (name "VCC") (class "Default")
      (node (ref "C201") (pin "P") (pinfunction "+_P") (pintype "passive"))
      (node (ref "F201") (pin "2") (pinfunction "2_2") (pintype "passive"))
      (node (ref "J202") (pin "1") (pinfunction "1_1") (pintype "passive"))
      (node (ref "J202") (pin "2") (pinfunction "2_2") (pintype "passive"))
      (node (ref "J202") (pin "3") (pinfunction "3_3") (pintype "passive"))
      (node (ref "J202") (pin "4") (pinfunction "4_4") (pintype "passive"))
    )
    (net (code "38") (name "VCC_") (class "Default")
      (node (ref "F201") (pin "1") (pinfunction "1_1") (pintype "passive"))
      (node (ref "J201") (pin "1") (pinfunction "1_1") (pintype "passive"))
      (node (ref "J201") (pin "2") (pinfunction "2_2") (pintype "passive"))
      (node (ref "J201") (pin "3") (pinfunction "3_3") (pintype "passive"))
      (node (ref "J201") (pin "4") (pinfunction "4_4") (pintype "passive"))
    )
    (net (code "39") (name "VOLTAGE_DATA_CON_N") (class "Default")
      (node (ref "J202") (pin "18") (pinfunction "18_18") (pintype "passive"))
      (node (ref "R202") (pin "1") (pinfunction "1_1") (pintype "passive"))
      (node (ref "U203") (pin "4") (pinfunction "RIN-_4") (pintype "input"))
    )
    (net (code "40") (name "VOLTAGE_DATA_CON_P") (class "Default")
      (node (ref "J202") (pin "17") (pinfunction "17_17") (pintype "passive"))
      (node (ref "R202") (pin "2") (pinfunction "2_2") (pintype "passive"))
      (node (ref "U203") (pin "3") (pinfunction "RIN+_3") (pintype "input"))
    )
    (net (code "41") (name "VOLTAGE_DATA_STM") (class "Default")
      (node (ref "C207") (pin "1") (pinfunction "1_1") (pintype "passive"))
      (node (ref "L202") (pin "1") (pinfunction "1_1") (pintype "passive"))
      (node (ref "U101") (pin "16") (pinfunction "PA6_16") (pintype "bidirectional"))
    )
    (net (code "42") (name "VOLTAGE_SCK_CON_N") (class "Default")
      (node (ref "J202") (pin "15") (pinfunction "15_15") (pintype "passive"))
      (node (ref "U204") (pin "3") (pinfunction "DOUT-_3") (pintype "output"))
    )
    (net (code "43") (name "VOLTAGE_SCK_CON_P") (class "Default")
      (node (ref "J202") (pin "16") (pinfunction "16_16") (pintype "passive"))
      (node (ref "U204") (pin "4") (pinfunction "DOUT+_4") (pintype "output"))
    )
    (net (code "44") (name "VOLTAGE_SCK_STM") (class "Default")
      (node (ref "U101") (pin "13") (pinfunction "PA3_13") (pintype "bidirectional"))
      (node (ref "U204") (pin "5") (pinfunction "DI_5") (pintype "input"))
    )
    (net (code "45") (name "unconnected-(J202-Pad9)") (class "Default")
      (node (ref "J202") (pin "9") (pinfunction "9_9") (pintype "passive"))
    )
    (net (code "46") (name "unconnected-(U101-PA0-Pad10)") (class "Default")
      (node (ref "U101") (pin "10") (pinfunction "PA0_10") (pintype "bidirectional"))
    )
    (net (code "47") (name "unconnected-(U101-PA1-Pad11)") (class "Default")
      (node (ref "U101") (pin "11") (pinfunction "PA1_11") (pintype "bidirectional"))
    )
    (net (code "48") (name "unconnected-(U101-PA2-Pad12)") (class "Default")
      (node (ref "U101") (pin "12") (pinfunction "PA2_12") (pintype "bidirectional"))
    )
    (net (code "49") (name "unconnected-(U101-PA4-Pad14)") (class "Default")
      (node (ref "U101") (pin "14") (pinfunction "PA4_14") (pintype "bidirectional"))
    )
    (net (code "50") (name "unconnected-(U101-PA5-Pad15)") (class "Default")
      (node (ref "U101") (pin "15") (pinfunction "PA5_15") (pintype "bidirectional"))
    )
    (net (code "51") (name "unconnected-(U101-PA12-Pad33)") (class "Default")
      (node (ref "U101") (pin "33") (pinfunction "PA12_33") (pintype "bidirectional"))
    )
    (net (code "52") (name "unconnected-(U101-PB2-Pad20)") (class "Default")
      (node (ref "U101") (pin "20") (pinfunction "PB2_20") (pintype "bidirectional"))
    )
    (net (code "53") (name "unconnected-(U101-PB9-Pad46)") (class "Default")
      (node (ref "U101") (pin "46") (pinfunction "PB9_46") (pintype "bidirectional"))
    )
    (net (code "54") (name "unconnected-(U101-PB10-Pad21)") (class "Default")
      (node (ref "U101") (pin "21") (pinfunction "PB10_21") (pintype "bidirectional"))
    )
    (net (code "55") (name "unconnected-(U101-PB11-Pad22)") (class "Default")
      (node (ref "U101") (pin "22") (pinfunction "PB11_22") (pintype "bidirectional"))
    )
    (net (code "56") (name "unconnected-(U101-PC13-Pad2)") (class "Default")
      (node (ref "U101") (pin "2") (pinfunction "PC13_2") (pintype "bidirectional"))
    )
    (net (code "57") (name "unconnected-(U101-PC14-Pad3)") (class "Default")
      (node (ref "U101") (pin "3") (pinfunction "PC14_3") (pintype "bidirectional"))
    )
    (net (code "58") (name "unconnected-(U101-PC15-Pad4)") (class "Default")
      (node (ref "U101") (pin "4") (pinfunction "PC15_4") (pintype "bidirectional"))
    )
    (net (code "59") (name "unconnected-(U101-PF1-Pad6)") (class "Default")
      (node (ref "U101") (pin "6") (pinfunction "PF1_6") (pintype "bidirectional"))
    )
  )
)
